# power.net
KiCad netlist of a schematic drawn in EAGLE
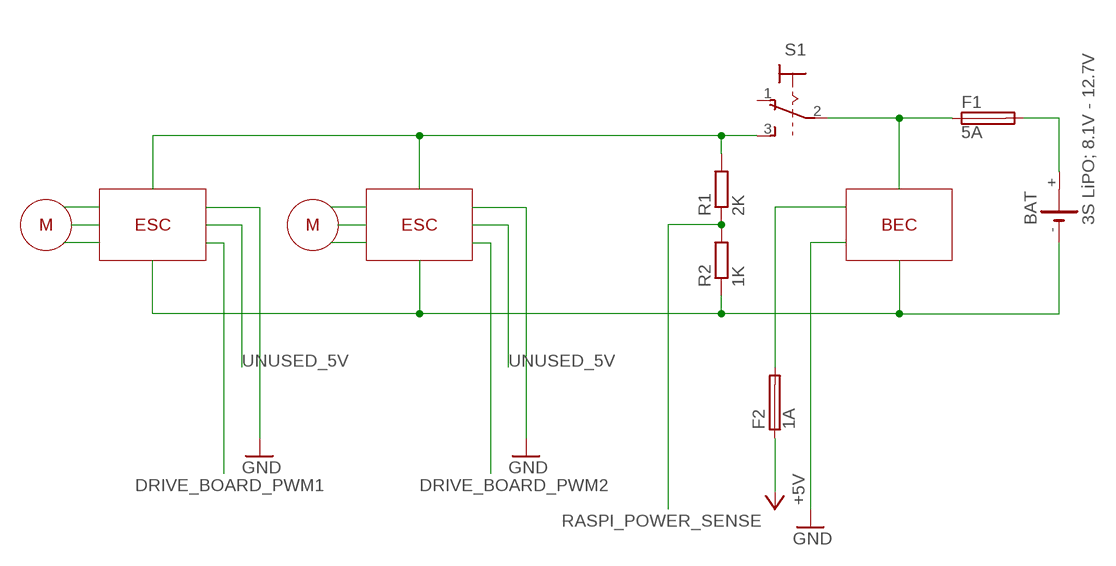
[diagram p0: schematic, sheet 1]

(export (version "E")
  (design (tool "Eeschema 10.0.6"))
  (components
    (comp (ref "BAT")
      (value "3S LiPO; 8.1V - 12.7V")
      (footprint "eagle-import:1V60R")
      (libsource (lib "eagle-import") (part "1V60R"))
    )
    (comp (ref "F1")
      (value "5A")
      (footprint "eagle-import:FUSE_HOLDER_MENTOR-1821")
      (libsource (lib "eagle-import") (part "FUSE1821"))
    )
    (comp (ref "F2")
      (value "1A")
      (footprint "eagle-import:FUSE_HOLDER_MENTOR-1821")
      (libsource (lib "eagle-import") (part "FUSE1821"))
    )
    (comp (ref "R1")
      (value "2K")
      (footprint "eagle-import:0204V")
      (libsource (lib "eagle-import") (part "R-EU_0204/2V"))
    )
    (comp (ref "R2")
      (value "1K")
      (footprint "eagle-import:0204V")
      (libsource (lib "eagle-import") (part "R-EU_0204/2V"))
    )
    (comp (ref "S1")
      (value "320-938")
      (footprint "eagle-import:320-938")
      (libsource (lib "eagle-import") (part "320-938"))
    )
  )
  (nets
    (net (code "1") (name "+5V") (class "Default")
      (node (ref "F2") (pin "A") (pinfunction "1_A") (pintype "passive"))
    )
    (net (code "4") (name "/RASPI_POWER_SENSE") (class "Default")
      (node (ref "R1") (pin "1") (pinfunction "1_1") (pintype "passive"))
      (node (ref "R2") (pin "2") (pinfunction "2_2") (pintype "passive"))
    )
    (net (code "7") (name "Net-(BAT-Pad-)") (class "Default")
      (node (ref "BAT") (pin "-") (pinfunction "-_-") (pintype "passive"))
      (node (ref "R2") (pin "1") (pinfunction "1_1") (pintype "passive"))
    )
    (net (code "8") (name "Net-(F1-1)") (class "Default")
      (node (ref "F1") (pin "A") (pinfunction "1_A") (pintype "passive"))
      (node (ref "S1") (pin "2") (pinfunction "P_2") (pintype "passive"))
    )
    (net (code "9") (name "Net-(F1-2)") (class "Default")
      (node (ref "BAT") (pin "+") (pinfunction "+_+") (pintype "passive"))
      (node (ref "F1") (pin "B") (pinfunction "2_B") (pintype "passive"))
    )
    (net (code "10") (name "Net-(S1A-S)") (class "Default")
      (node (ref "R1") (pin "2") (pinfunction "2_2") (pintype "passive"))
      (node (ref "S1") (pin "3") (pinfunction "S_3") (pintype "passive"))
    )
    (net (code "11") (name "unconnected-(BAT-+-Pad+@1)") (class "Default")
      (node (ref "BAT") (pin "+@1") (pinfunction "+_+@1") (pintype "passive"))
    )
    (net (code "12") (name "unconnected-(F2-2-PadB)") (class "Default")
      (node (ref "F2") (pin "B") (pinfunction "2_B") (pintype "passive"))
    )
    (net (code "13") (name "unconnected-(S1A-O-Pad1)") (class "Default")
      (node (ref "S1") (pin "1") (pinfunction "O_1") (pintype "passive"))
    )
  )
)
